# Qwiic_Pressure_Sensor_-_LPS25HB.net
KiCad netlist of a schematic drawn in EAGLE
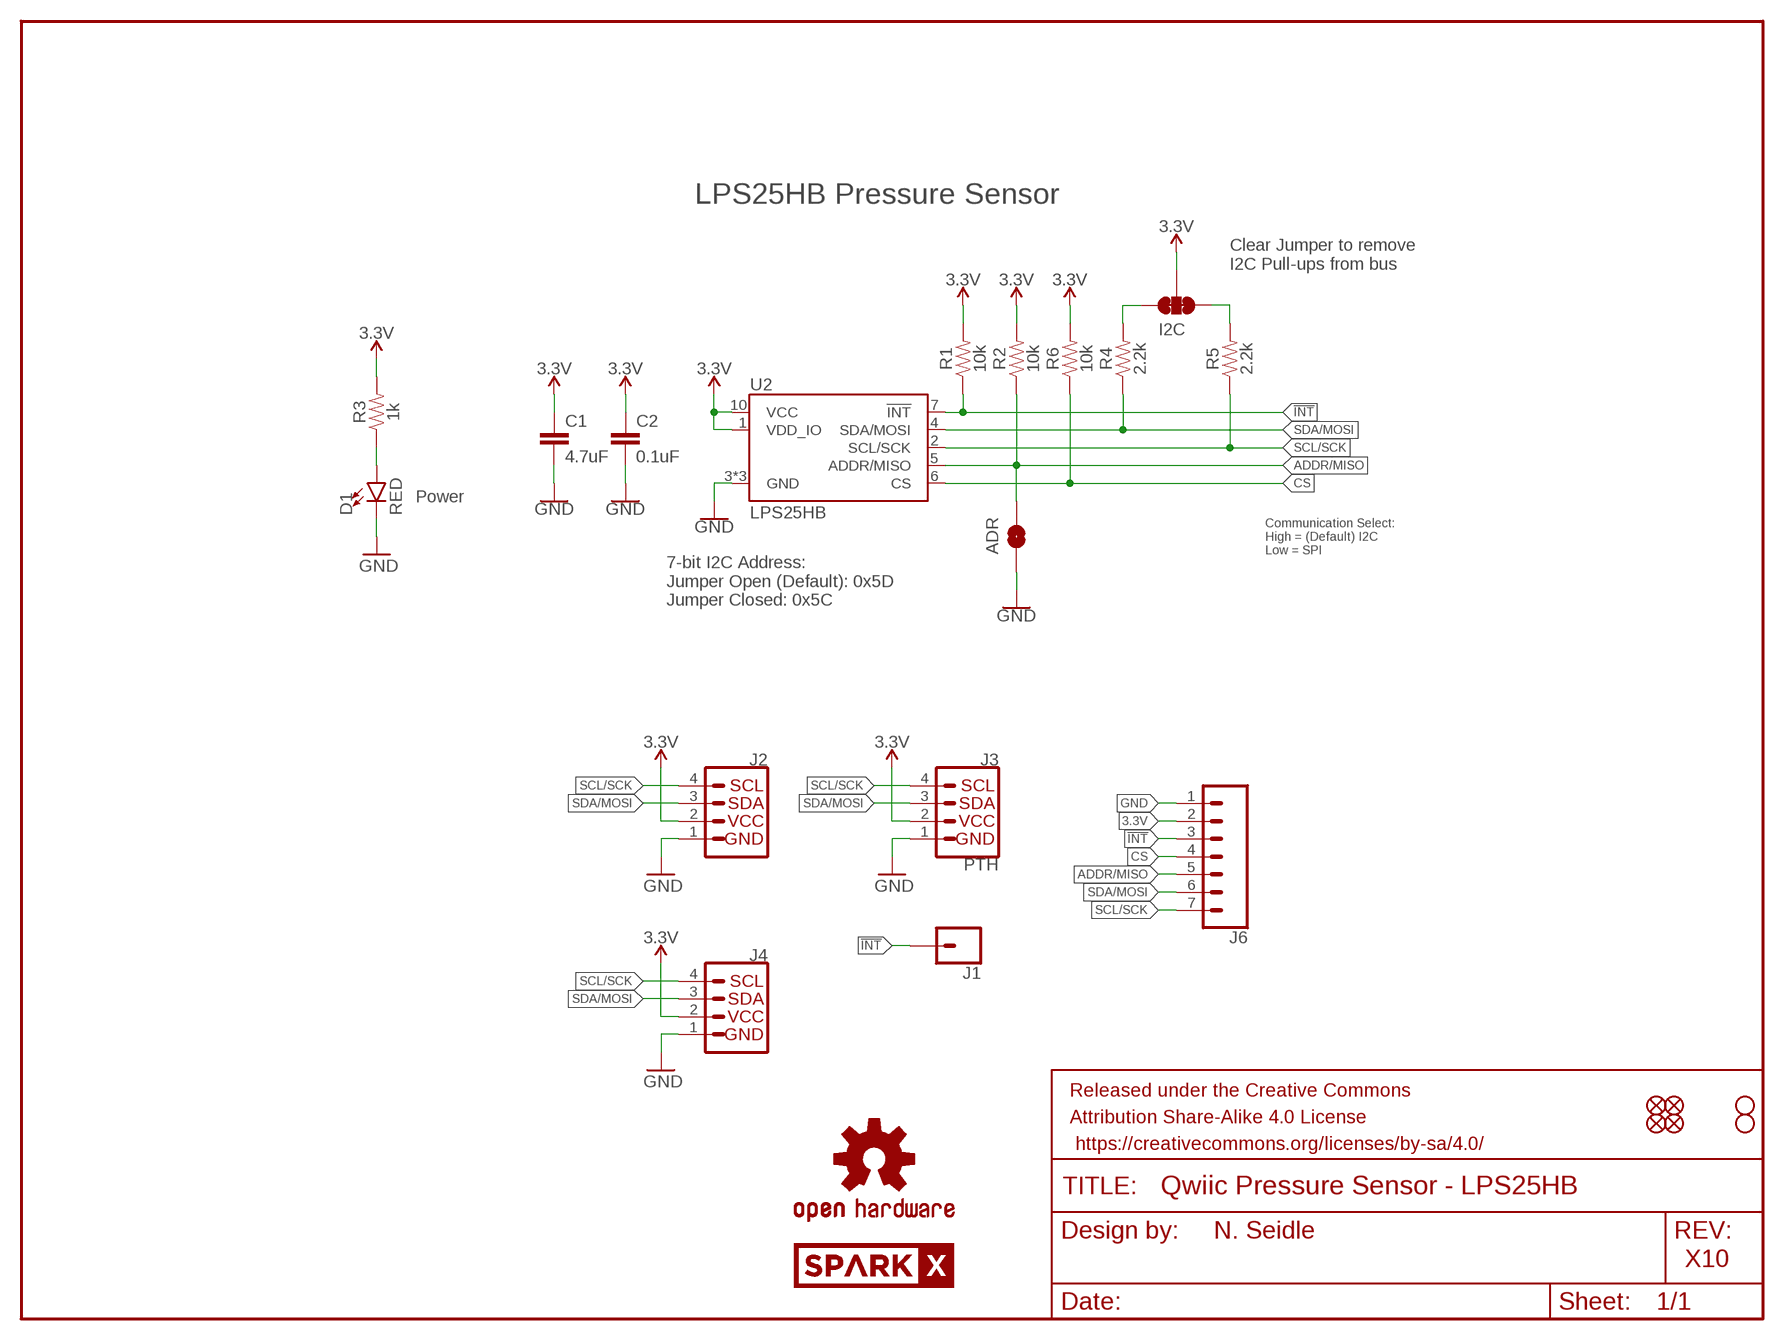
[diagram p0: schematic, sheet 1]

(export (version "E")
  (design (tool "Eeschema 10.0.6"))
  (components
    (comp (ref "ADR")
      (value "JUMPER-SMT_2_NO_SILK")
      (footprint "eagle-import:SMT-JUMPER_2_NO_SILK")
      (libsource (lib "eagle-import") (part "JUMPER-SMT_2_NO_SILK"))
    )
    (comp (ref "C1")
      (value "4.7uF")
      (footprint "eagle-import:0603")
      (libsource (lib "eagle-import") (part "4.7UF0603"))
    )
    (comp (ref "C2")
      (value "0.1uF")
      (footprint "eagle-import:0603")
      (libsource (lib "eagle-import") (part "0.1UF-0603-25V-(+80/-20%)"))
    )
    (comp (ref "D1")
      (value "RED")
      (footprint "eagle-import:LED-0603")
      (libsource (lib "eagle-import") (part "LED-RED0603"))
    )
    (comp (ref "FRAME1")
      (value "FRAME-LETTER")
      (footprint "eagle-import:CREATIVE_COMMONS")
      (libsource (lib "eagle-import") (part "FRAME-LETTER"))
    )
    (comp (ref "I2C")
      (value "JUMPER-SMT_3_2-NC_TRACE_SILK")
      (footprint "eagle-import:SMT-JUMPER_3_2-NC_TRACE_SILK")
      (libsource (lib "eagle-import") (part "JUMPER-SMT_3_2-NC_TRACE_SILK"))
    )
    (comp (ref "J1")
      (value "CONN_01PTH_NO_SILK_YES_STOP")
      (footprint "eagle-import:1X01_NO_SILK")
      (libsource (lib "eagle-import") (part "CONN_01PTH_NO_SILK_YES_STOP"))
    )
    (comp (ref "J2")
      (value "I2C_STANDARDQWIIC")
      (footprint "eagle-import:1X04_1MM_RA")
      (libsource (lib "eagle-import") (part "I2C_STANDARDQWIIC"))
    )
    (comp (ref "J3")
      (value "PTH")
      (footprint "eagle-import:1X04_NO_SILK")
      (libsource (lib "eagle-import") (part "SparkX_I2C_STANDARD_NO_SILK"))
    )
    (comp (ref "J4")
      (value "I2C_STANDARDQWIIC")
      (footprint "eagle-import:1X04_1MM_RA")
      (libsource (lib "eagle-import") (part "I2C_STANDARDQWIIC"))
    )
    (comp (ref "J6")
      (value "CONN_07NO_SILK")
      (footprint "eagle-import:1X07_NO_SILK")
      (libsource (lib "eagle-import") (part "CONN_07NO_SILK"))
    )
    (comp (ref "JP1")
      (value "FIDUCIALUFIDUCIAL")
      (footprint "eagle-import:MICRO-FIDUCIAL")
      (libsource (lib "eagle-import") (part "FIDUCIALUFIDUCIAL"))
    )
    (comp (ref "JP2")
      (value "FIDUCIALUFIDUCIAL")
      (footprint "eagle-import:MICRO-FIDUCIAL")
      (libsource (lib "eagle-import") (part "FIDUCIALUFIDUCIAL"))
    )
    (comp (ref "JP3")
      (value "STAND-OFF")
      (footprint "eagle-import:STAND-OFF")
      (libsource (lib "eagle-import") (part "STAND-OFF"))
    )
    (comp (ref "JP4")
      (value "STAND-OFF")
      (footprint "eagle-import:STAND-OFF")
      (libsource (lib "eagle-import") (part "STAND-OFF"))
    )
    (comp (ref "JP5")
      (value "FIDUCIALUFIDUCIAL")
      (footprint "eagle-import:MICRO-FIDUCIAL")
      (libsource (lib "eagle-import") (part "FIDUCIALUFIDUCIAL"))
    )
    (comp (ref "JP6")
      (value "FIDUCIALUFIDUCIAL")
      (footprint "eagle-import:MICRO-FIDUCIAL")
      (libsource (lib "eagle-import") (part "FIDUCIALUFIDUCIAL"))
    )
    (comp (ref "LOGO1")
      (value "OSHW-LOGOMINI")
      (footprint "eagle-import:OSHW-LOGO-MINI")
      (libsource (lib "eagle-import") (part "OSHW-LOGOMINI"))
    )
    (comp (ref "R1")
      (value "10k")
      (footprint "eagle-import:0603")
      (libsource (lib "eagle-import") (part "10KOHM-0603-1/10W-1%"))
    )
    (comp (ref "R2")
      (value "10k")
      (footprint "eagle-import:0603")
      (libsource (lib "eagle-import") (part "10KOHM-0603-1/10W-1%"))
    )
    (comp (ref "R3")
      (value "1k")
      (footprint "eagle-import:0603")
      (libsource (lib "eagle-import") (part "1KOHM-0603-1/10W-1%"))
    )
    (comp (ref "R4")
      (value "2.2k")
      (footprint "eagle-import:0603")
      (libsource (lib "eagle-import") (part "2.2KOHM-0603-1/10W-1%"))
    )
    (comp (ref "R5")
      (value "2.2k")
      (footprint "eagle-import:0603")
      (libsource (lib "eagle-import") (part "2.2KOHM-0603-1/10W-1%"))
    )
    (comp (ref "R6")
      (value "10k")
      (footprint "eagle-import:0603")
      (libsource (lib "eagle-import") (part "10KOHM-0603-1/10W-1%"))
    )
    (comp (ref "U$2")
      (value "SPARKX-LOGO4")
      (footprint "eagle-import:SPARKX-MEDIUM")
      (libsource (lib "eagle-import") (part "SPARKX-LOGO4"))
    )
    (comp (ref "U2")
      (value "LPS25HB")
      (footprint "eagle-import:LPS25HB")
      (libsource (lib "eagle-import") (part "LPS25HB"))
    )
  )
  (nets
    (net (code "1") (name "/~{INT}") (class "Default")
      (node (ref "J1") (pin "1") (pinfunction "1_1") (pintype "passive"))
      (node (ref "J6") (pin "3") (pinfunction "3_3") (pintype "passive"))
      (node (ref "R1") (pin "1") (pinfunction "1_1") (pintype "passive"))
      (node (ref "U2") (pin "7") (pinfunction "~{INT}_7") (pintype "bidirectional"))
    )
    (net (code "2") (name "3.3V") (class "Default")
      (node (ref "C1") (pin "1") (pinfunction "1_1") (pintype "passive"))
      (node (ref "C2") (pin "1") (pinfunction "1_1") (pintype "passive"))
      (node (ref "I2C") (pin "2") (pinfunction "2_2") (pintype "passive"))
      (node (ref "J2") (pin "2") (pinfunction "2_2") (pintype "power_in"))
      (node (ref "J3") (pin "2") (pinfunction "VCC_2") (pintype "power_in"))
      (node (ref "J4") (pin "2") (pinfunction "2_2") (pintype "power_in"))
      (node (ref "J6") (pin "2") (pinfunction "2_2") (pintype "passive"))
      (node (ref "R1") (pin "2") (pinfunction "2_2") (pintype "passive"))
      (node (ref "R2") (pin "2") (pinfunction "2_2") (pintype "passive"))
      (node (ref "R3") (pin "2") (pinfunction "2_2") (pintype "passive"))
      (node (ref "R6") (pin "2") (pinfunction "2_2") (pintype "passive"))
      (node (ref "U2") (pin "1") (pinfunction "VDD_IO_1") (pintype "bidirectional"))
      (node (ref "U2") (pin "10") (pinfunction "VCC_10") (pintype "bidirectional"))
    )
    (net (code "3") (name "ADDR{slash}MISO") (class "Default")
      (node (ref "ADR") (pin "2") (pinfunction "2_2") (pintype "passive"))
      (node (ref "J6") (pin "5") (pinfunction "5_5") (pintype "passive"))
      (node (ref "R2") (pin "1") (pinfunction "1_1") (pintype "passive"))
      (node (ref "U2") (pin "5") (pinfunction "ADDR/MISO_5") (pintype "bidirectional"))
    )
    (net (code "4") (name "CS") (class "Default")
      (node (ref "J6") (pin "4") (pinfunction "4_4") (pintype "passive"))
      (node (ref "R6") (pin "1") (pinfunction "1_1") (pintype "passive"))
      (node (ref "U2") (pin "6") (pinfunction "CS_6") (pintype "bidirectional"))
    )
    (net (code "5") (name "GND") (class "Default")
      (node (ref "ADR") (pin "1") (pinfunction "1_1") (pintype "passive"))
      (node (ref "C1") (pin "2") (pinfunction "2_2") (pintype "passive"))
      (node (ref "C2") (pin "2") (pinfunction "2_2") (pintype "passive"))
      (node (ref "D1") (pin "C") (pinfunction "C_C") (pintype "passive"))
      (node (ref "J2") (pin "1") (pinfunction "1_1") (pintype "power_in"))
      (node (ref "J3") (pin "1") (pinfunction "GND_1") (pintype "power_in"))
      (node (ref "J4") (pin "1") (pinfunction "1_1") (pintype "power_in"))
      (node (ref "J6") (pin "1") (pinfunction "1_1") (pintype "passive"))
      (node (ref "U2") (pin "3") (pinfunction "GND_3") (pintype "bidirectional"))
      (node (ref "U2") (pin "8") (pinfunction "GND_8") (pintype "bidirectional"))
      (node (ref "U2") (pin "9") (pinfunction "GND_9") (pintype "bidirectional"))
    )
    (net (code "6") (name "Net-(D1-PadA)") (class "Default")
      (node (ref "D1") (pin "A") (pinfunction "A_A") (pintype "passive"))
      (node (ref "R3") (pin "1") (pinfunction "1_1") (pintype "passive"))
    )
    (net (code "7") (name "Net-(I2C-Pad1)") (class "Default")
      (node (ref "I2C") (pin "1") (pinfunction "1_1") (pintype "passive"))
      (node (ref "R5") (pin "2") (pinfunction "2_2") (pintype "passive"))
    )
    (net (code "8") (name "Net-(I2C-Pad3)") (class "Default")
      (node (ref "I2C") (pin "3") (pinfunction "3_3") (pintype "passive"))
      (node (ref "R4") (pin "2") (pinfunction "2_2") (pintype "passive"))
    )
    (net (code "9") (name "SCL{slash}SCK") (class "Default")
      (node (ref "J2") (pin "4") (pinfunction "4_4") (pintype "passive"))
      (node (ref "J3") (pin "4") (pinfunction "SCL_4") (pintype "passive"))
      (node (ref "J4") (pin "4") (pinfunction "4_4") (pintype "passive"))
      (node (ref "J6") (pin "7") (pinfunction "7_7") (pintype "passive"))
      (node (ref "R5") (pin "1") (pinfunction "1_1") (pintype "passive"))
      (node (ref "U2") (pin "2") (pinfunction "SCL/SCK_2") (pintype "bidirectional"))
    )
    (net (code "10") (name "SDA{slash}MOSI") (class "Default")
      (node (ref "J2") (pin "3") (pinfunction "3_3") (pintype "passive"))
      (node (ref "J3") (pin "3") (pinfunction "SDA_3") (pintype "passive"))
      (node (ref "J4") (pin "3") (pinfunction "3_3") (pintype "passive"))
      (node (ref "J6") (pin "6") (pinfunction "6_6") (pintype "passive"))
      (node (ref "R4") (pin "1") (pinfunction "1_1") (pintype "passive"))
      (node (ref "U2") (pin "4") (pinfunction "SDA/MOSI_4") (pintype "bidirectional"))
    )
  )
)
